# encore_Main_Board_v2.net
KiCad netlist of a schematic drawn in EAGLE
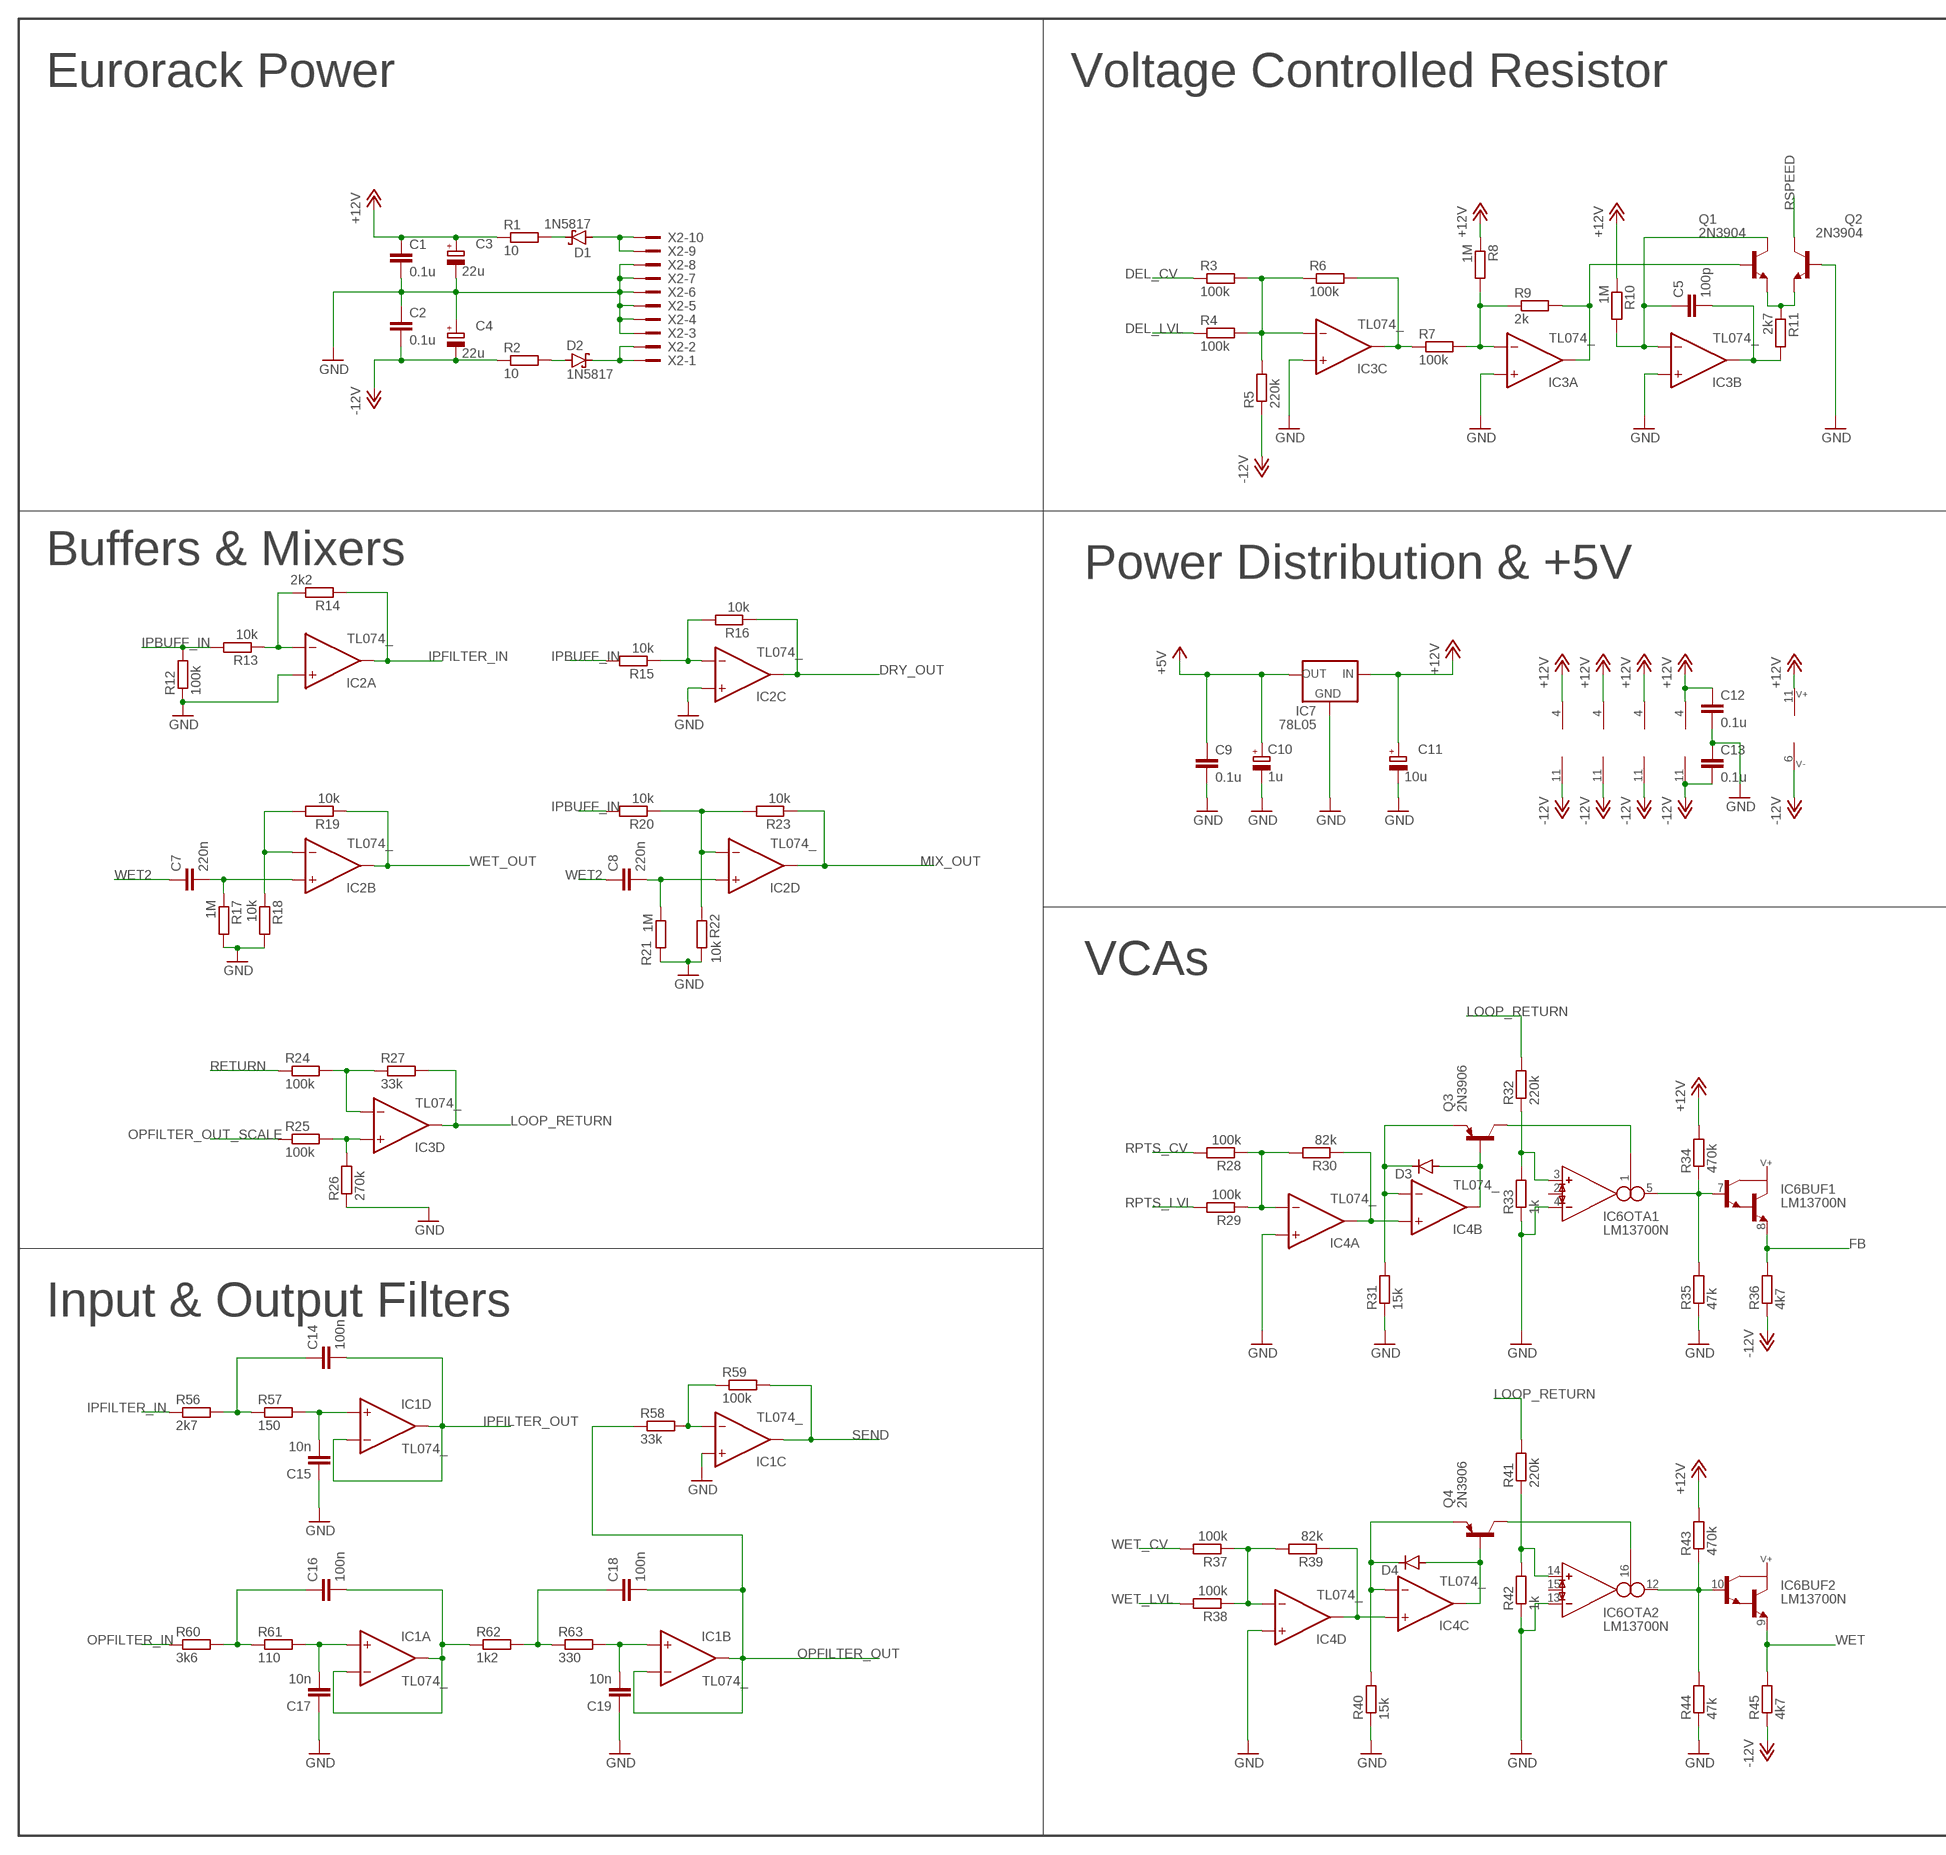
[diagram p0: schematic, sheet 1, part 1 of 2]
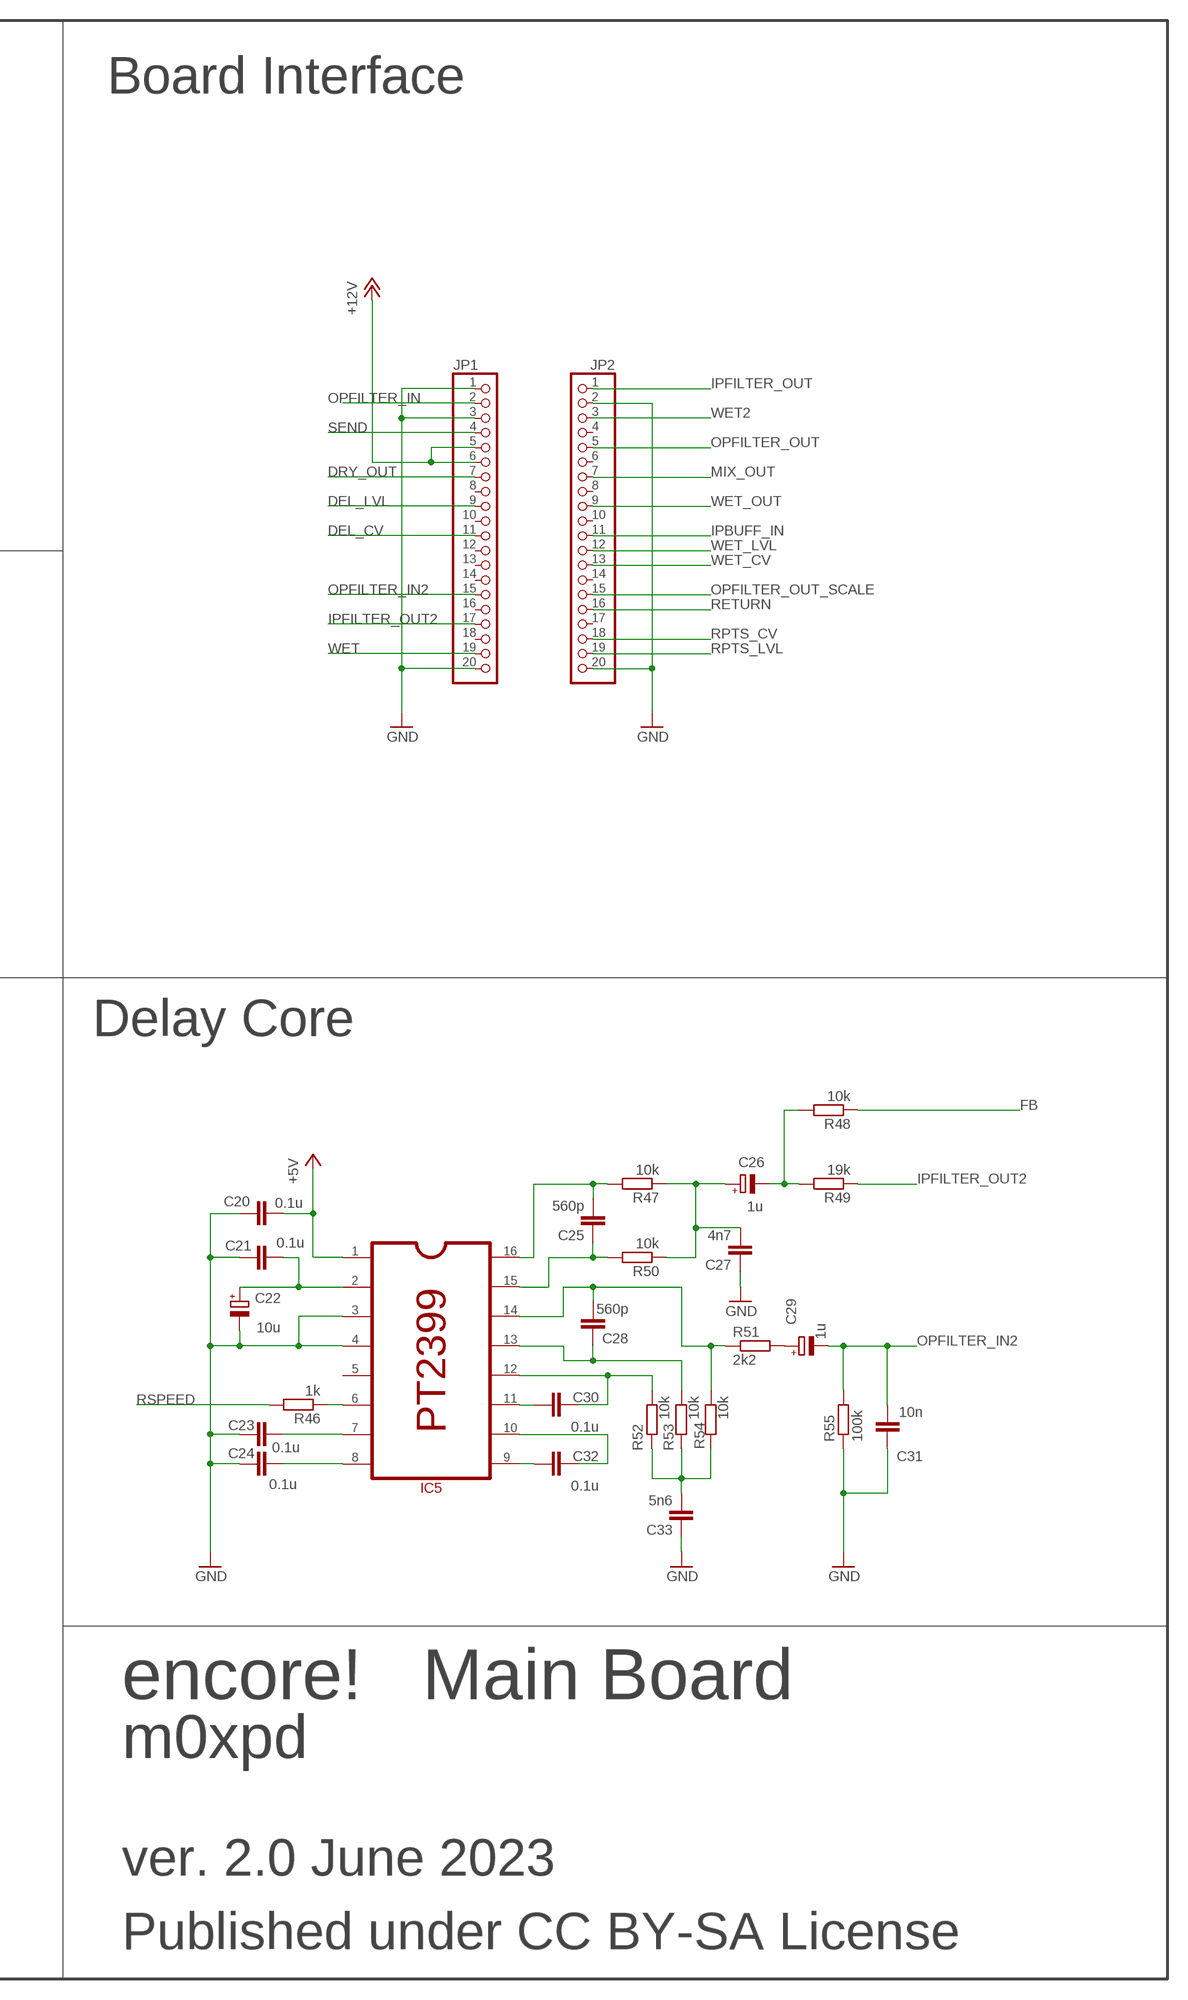
[diagram p1: schematic, sheet 1, part 2 of 2]

(export (version "E")
  (design (tool "Eeschema 10.0.6"))
  (components
    (comp (ref "C1")
      (value "0.1u")
      (footprint "eagle-import:C050-025X075")
      (libsource (lib "eagle-import") (part "C-EU050-025X075"))
    )
    (comp (ref "C2")
      (value "0.1u")
      (footprint "eagle-import:C050-025X075")
      (libsource (lib "eagle-import") (part "C-EU050-025X075"))
    )
    (comp (ref "C3")
      (value "22u")
      (footprint "eagle-import:E2,5-5")
      (libsource (lib "eagle-import") (part "CPOL-EUE2.5-5"))
    )
    (comp (ref "C4")
      (value "22u")
      (footprint "eagle-import:E2,5-5")
      (libsource (lib "eagle-import") (part "CPOL-EUE2.5-5"))
    )
    (comp (ref "C5")
      (value "100p")
      (footprint "eagle-import:C025-025X050")
      (libsource (lib "eagle-import") (part "C-EU025-025X050"))
    )
    (comp (ref "C7")
      (value "220n")
      (footprint "eagle-import:C050-024X044")
      (libsource (lib "eagle-import") (part "C-EU050-024X044"))
    )
    (comp (ref "C8")
      (value "220n")
      (footprint "eagle-import:C050-024X044")
      (libsource (lib "eagle-import") (part "C-EU050-024X044"))
    )
    (comp (ref "C9")
      (value "0.1u")
      (footprint "eagle-import:C050-025X075")
      (libsource (lib "eagle-import") (part "C-EU050-025X075"))
    )
    (comp (ref "C10")
      (value "1u")
      (footprint "eagle-import:E2,5-5")
      (libsource (lib "eagle-import") (part "CPOL-EUE2.5-5"))
    )
    (comp (ref "C11")
      (value "10u")
      (footprint "eagle-import:E2,5-5")
      (libsource (lib "eagle-import") (part "CPOL-EUE2.5-5"))
    )
    (comp (ref "C12")
      (value "0.1u")
      (footprint "eagle-import:C050-025X075")
      (libsource (lib "eagle-import") (part "C-EU050-025X075"))
    )
    (comp (ref "C13")
      (value "0.1u")
      (footprint "eagle-import:C050-025X075")
      (libsource (lib "eagle-import") (part "C-EU050-025X075"))
    )
    (comp (ref "C14")
      (value "100n")
      (footprint "eagle-import:C025-025X050")
      (libsource (lib "eagle-import") (part "C-EU025-025X050"))
    )
    (comp (ref "C15")
      (value "10n")
      (footprint "eagle-import:C025-025X050")
      (libsource (lib "eagle-import") (part "C-EU025-025X050"))
    )
    (comp (ref "C16")
      (value "100n")
      (footprint "eagle-import:C025-025X050")
      (libsource (lib "eagle-import") (part "C-EU025-025X050"))
    )
    (comp (ref "C17")
      (value "10n")
      (footprint "eagle-import:C025-025X050")
      (libsource (lib "eagle-import") (part "C-EU025-025X050"))
    )
    (comp (ref "C18")
      (value "100n")
      (footprint "eagle-import:C025-025X050")
      (libsource (lib "eagle-import") (part "C-EU025-025X050"))
    )
    (comp (ref "C19")
      (value "10n")
      (footprint "eagle-import:C025-025X050")
      (libsource (lib "eagle-import") (part "C-EU025-025X050"))
    )
    (comp (ref "C20")
      (value "0.1u")
      (footprint "eagle-import:C050-025X075")
      (libsource (lib "eagle-import") (part "C-EU050-025X075"))
    )
    (comp (ref "C21")
      (value "0.1u")
      (footprint "eagle-import:C050-025X075")
      (libsource (lib "eagle-import") (part "C-EU050-025X075"))
    )
    (comp (ref "C22")
      (value "10u")
      (footprint "eagle-import:E2,5-5")
      (libsource (lib "eagle-import") (part "CPOL-EUE2.5-5"))
    )
    (comp (ref "C23")
      (value "0.1u")
      (footprint "eagle-import:C050-025X075")
      (libsource (lib "eagle-import") (part "C-EU050-025X075"))
    )
    (comp (ref "C24")
      (value "0.1u")
      (footprint "eagle-import:C050-025X075")
      (libsource (lib "eagle-import") (part "C-EU050-025X075"))
    )
    (comp (ref "C25")
      (value "560p")
      (footprint "eagle-import:C025-025X050")
      (libsource (lib "eagle-import") (part "C-EU025-025X050"))
    )
    (comp (ref "C26")
      (value "1u")
      (footprint "eagle-import:E2,5-5")
      (libsource (lib "eagle-import") (part "CPOL-EUE2.5-5"))
    )
    (comp (ref "C27")
      (value "4n7")
      (footprint "eagle-import:C050-025X075")
      (libsource (lib "eagle-import") (part "C-EU050-025X075"))
    )
    (comp (ref "C28")
      (value "560p")
      (footprint "eagle-import:C025-025X050")
      (libsource (lib "eagle-import") (part "C-EU025-025X050"))
    )
    (comp (ref "C29")
      (value "1u")
      (footprint "eagle-import:E2,5-5")
      (libsource (lib "eagle-import") (part "CPOL-EUE2.5-5"))
    )
    (comp (ref "C30")
      (value "0.1u")
      (footprint "eagle-import:C050-025X075")
      (libsource (lib "eagle-import") (part "C-EU050-025X075"))
    )
    (comp (ref "C31")
      (value "10n")
      (footprint "eagle-import:C025-025X050")
      (libsource (lib "eagle-import") (part "C-EU025-025X050"))
    )
    (comp (ref "C32")
      (value "0.1u")
      (footprint "eagle-import:C050-025X075")
      (libsource (lib "eagle-import") (part "C-EU050-025X075"))
    )
    (comp (ref "C33")
      (value "5n6")
      (footprint "eagle-import:C050-025X075")
      (libsource (lib "eagle-import") (part "C-EU050-025X075"))
    )
    (comp (ref "D1")
      (value "1N5817")
      (footprint "eagle-import:DO35-7")
      (libsource (lib "eagle-import") (part "SCHOTTKY-DIODEDO35-7"))
    )
    (comp (ref "D2")
      (value "1N5817")
      (footprint "eagle-import:DO35-7")
      (libsource (lib "eagle-import") (part "SCHOTTKY-DIODEDO35-7"))
    )
    (comp (ref "D3")
      (value "1N4148DO35-7")
      (footprint "eagle-import:DO35-7")
      (libsource (lib "eagle-import") (part "1N4148DO35-7"))
    )
    (comp (ref "D4")
      (value "1N4148DO35-7")
      (footprint "eagle-import:DO35-7")
      (libsource (lib "eagle-import") (part "1N4148DO35-7"))
    )
    (comp (ref "IC1")
      (value "TL074_")
      (footprint "eagle-import:DIL14")
      (libsource (lib "eagle-import") (part "TL074_"))
    )
    (comp (ref "IC2")
      (value "TL074_")
      (footprint "eagle-import:DIL14")
      (libsource (lib "eagle-import") (part "TL074_"))
    )
    (comp (ref "IC3")
      (value "TL074_")
      (footprint "eagle-import:DIL14")
      (libsource (lib "eagle-import") (part "TL074_"))
    )
    (comp (ref "IC4")
      (value "TL074_")
      (footprint "eagle-import:DIL14")
      (libsource (lib "eagle-import") (part "TL074_"))
    )
    (comp (ref "IC5")
      (value "PT2399")
      (footprint "eagle-import:DIP-16")
      (libsource (lib "eagle-import") (part "PT2399"))
    )
    (comp (ref "IC6")
      (value "LM13700N")
      (footprint "eagle-import:DIL16")
      (libsource (lib "eagle-import") (part "LM13700N"))
    )
    (comp (ref "IC7")
      (value "78L05")
      (footprint "eagle-import:78LXX")
      (libsource (lib "eagle-import") (part "78LXX"))
    )
    (comp (ref "JP1")
      (value "PINHD-1X20")
      (footprint "eagle-import:1X20")
      (libsource (lib "eagle-import") (part "PINHD-1X20"))
    )
    (comp (ref "JP2")
      (value "PINHD-1X20")
      (footprint "eagle-import:1X20")
      (libsource (lib "eagle-import") (part "PINHD-1X20"))
    )
    (comp (ref "Q1")
      (value "2N3904")
      (footprint "eagle-import:TO92")
      (libsource (lib "eagle-import") (part "2N3904"))
    )
    (comp (ref "Q2")
      (value "2N3904")
      (footprint "eagle-import:TO92")
      (libsource (lib "eagle-import") (part "2N3904"))
    )
    (comp (ref "Q3")
      (value "2N3906")
      (footprint "eagle-import:TO92")
      (libsource (lib "eagle-import") (part "2N3906"))
    )
    (comp (ref "Q4")
      (value "2N3906")
      (footprint "eagle-import:TO92")
      (libsource (lib "eagle-import") (part "2N3906"))
    )
    (comp (ref "R1")
      (value "10")
      (footprint "eagle-import:0204_7")
      (libsource (lib "eagle-import") (part "R-EU_0204/7"))
    )
    (comp (ref "R2")
      (value "10")
      (footprint "eagle-import:0204_7")
      (libsource (lib "eagle-import") (part "R-EU_0204/7"))
    )
    (comp (ref "R3")
      (value "100k")
      (footprint "eagle-import:0204_7")
      (libsource (lib "eagle-import") (part "R-EU_0204/7"))
    )
    (comp (ref "R4")
      (value "100k")
      (footprint "eagle-import:0204_7")
      (libsource (lib "eagle-import") (part "R-EU_0204/7"))
    )
    (comp (ref "R5")
      (value "220k")
      (footprint "eagle-import:0204_7")
      (libsource (lib "eagle-import") (part "R-EU_0204/7"))
    )
    (comp (ref "R6")
      (value "100k")
      (footprint "eagle-import:0204_7")
      (libsource (lib "eagle-import") (part "R-EU_0204/7"))
    )
    (comp (ref "R7")
      (value "100k")
      (footprint "eagle-import:0204_7")
      (libsource (lib "eagle-import") (part "R-EU_0204/7"))
    )
    (comp (ref "R8")
      (value "1M")
      (footprint "eagle-import:0204_7")
      (libsource (lib "eagle-import") (part "R-EU_0204/7"))
    )
    (comp (ref "R9")
      (value "2k")
      (footprint "eagle-import:0204_7")
      (libsource (lib "eagle-import") (part "R-EU_0204/7"))
    )
    (comp (ref "R10")
      (value "1M")
      (footprint "eagle-import:0204_7")
      (libsource (lib "eagle-import") (part "R-EU_0204/7"))
    )
    (comp (ref "R11")
      (value "2k7")
      (footprint "eagle-import:0204_7")
      (libsource (lib "eagle-import") (part "R-EU_0204/7"))
    )
    (comp (ref "R12")
      (value "100k")
      (footprint "eagle-import:0204_7")
      (libsource (lib "eagle-import") (part "R-EU_0204/7"))
    )
    (comp (ref "R13")
      (value "10k")
      (footprint "eagle-import:0204_7")
      (libsource (lib "eagle-import") (part "R-EU_0204/7"))
    )
    (comp (ref "R14")
      (value "2k2")
      (footprint "eagle-import:0204_7")
      (libsource (lib "eagle-import") (part "R-EU_0204/7"))
    )
    (comp (ref "R15")
      (value "10k")
      (footprint "eagle-import:0204_7")
      (libsource (lib "eagle-import") (part "R-EU_0204/7"))
    )
    (comp (ref "R16")
      (value "10k")
      (footprint "eagle-import:0204_7")
      (libsource (lib "eagle-import") (part "R-EU_0204/7"))
    )
    (comp (ref "R17")
      (value "1M")
      (footprint "eagle-import:0204_7")
      (libsource (lib "eagle-import") (part "R-EU_0204/7"))
    )
    (comp (ref "R18")
      (value "10k")
      (footprint "eagle-import:0204_7")
      (libsource (lib "eagle-import") (part "R-EU_0204/7"))
    )
    (comp (ref "R19")
      (value "10k")
      (footprint "eagle-import:0204_7")
      (libsource (lib "eagle-import") (part "R-EU_0204/7"))
    )
    (comp (ref "R20")
      (value "10k")
      (footprint "eagle-import:0204_7")
      (libsource (lib "eagle-import") (part "R-EU_0204/7"))
    )
    (comp (ref "R21")
      (value "1M")
      (footprint "eagle-import:0204_7")
      (libsource (lib "eagle-import") (part "R-EU_0204/7"))
    )
    (comp (ref "R22")
      (value "10k")
      (footprint "eagle-import:0204_7")
      (libsource (lib "eagle-import") (part "R-EU_0204/7"))
    )
    (comp (ref "R23")
      (value "10k")
      (footprint "eagle-import:0204_7")
      (libsource (lib "eagle-import") (part "R-EU_0204/7"))
    )
    (comp (ref "R24")
      (value "100k")
      (footprint "eagle-import:0204_7")
      (libsource (lib "eagle-import") (part "R-EU_0204/7"))
    )
    (comp (ref "R25")
      (value "100k")
      (footprint "eagle-import:0204_7")
      (libsource (lib "eagle-import") (part "R-EU_0204/7"))
    )
    (comp (ref "R26")
      (value "270k")
      (footprint "eagle-import:0204_7")
      (libsource (lib "eagle-import") (part "R-EU_0204/7"))
    )
    (comp (ref "R27")
      (value "33k")
      (footprint "eagle-import:0204_7")
      (libsource (lib "eagle-import") (part "R-EU_0204/7"))
    )
    (comp (ref "R28")
      (value "100k")
      (footprint "eagle-import:0204_7")
      (libsource (lib "eagle-import") (part "R-EU_0204/7"))
    )
    (comp (ref "R29")
      (value "100k")
      (footprint "eagle-import:0204_7")
      (libsource (lib "eagle-import") (part "R-EU_0204/7"))
    )
    (comp (ref "R30")
      (value "82k")
      (footprint "eagle-import:0204_7")
      (libsource (lib "eagle-import") (part "R-EU_0204/7"))
    )
    (comp (ref "R31")
      (value "15k")
      (footprint "eagle-import:0204_7")
      (libsource (lib "eagle-import") (part "R-EU_0204/7"))
    )
    (comp (ref "R32")
      (value "220k")
      (footprint "eagle-import:0204_7")
      (libsource (lib "eagle-import") (part "R-EU_0204/7"))
    )
    (comp (ref "R33")
      (value "1k")
      (footprint "eagle-import:0204_7")
      (libsource (lib "eagle-import") (part "R-EU_0204/7"))
    )
    (comp (ref "R34")
      (value "470k")
      (footprint "eagle-import:0204_7")
      (libsource (lib "eagle-import") (part "R-EU_0204/7"))
    )
    (comp (ref "R35")
      (value "47k")
      (footprint "eagle-import:0204_7")
      (libsource (lib "eagle-import") (part "R-EU_0204/7"))
    )
    (comp (ref "R36")
      (value "4k7")
      (footprint "eagle-import:0204_7")
      (libsource (lib "eagle-import") (part "R-EU_0204/7"))
    )
    (comp (ref "R37")
      (value "100k")
      (footprint "eagle-import:0204_7")
      (libsource (lib "eagle-import") (part "R-EU_0204/7"))
    )
    (comp (ref "R38")
      (value "100k")
      (footprint "eagle-import:0204_7")
      (libsource (lib "eagle-import") (part "R-EU_0204/7"))
    )
    (comp (ref "R39")
      (value "82k")
      (footprint "eagle-import:0204_7")
      (libsource (lib "eagle-import") (part "R-EU_0204/7"))
    )
    (comp (ref "R40")
      (value "15k")
      (footprint "eagle-import:0204_7")
      (libsource (lib "eagle-import") (part "R-EU_0204/7"))
    )
    (comp (ref "R41")
      (value "220k")
      (footprint "eagle-import:0204_7")
      (libsource (lib "eagle-import") (part "R-EU_0204/7"))
    )
    (comp (ref "R42")
      (value "1k")
      (footprint "eagle-import:0204_7")
      (libsource (lib "eagle-import") (part "R-EU_0204/7"))
    )
    (comp (ref "R43")
      (value "470k")
      (footprint "eagle-import:0204_7")
      (libsource (lib "eagle-import") (part "R-EU_0204/7"))
    )
    (comp (ref "R44")
      (value "47k")
      (footprint "eagle-import:0204_7")
      (libsource (lib "eagle-import") (part "R-EU_0204/7"))
    )
    (comp (ref "R45")
      (value "4k7")
      (footprint "eagle-import:0204_7")
      (libsource (lib "eagle-import") (part "R-EU_0204/7"))
    )
    (comp (ref "R46")
      (value "1k")
      (footprint "eagle-import:0204_7")
      (libsource (lib "eagle-import") (part "R-EU_0204/7"))
    )
    (comp (ref "R47")
      (value "10k")
      (footprint "eagle-import:0204_7")
      (libsource (lib "eagle-import") (part "R-EU_0204/7"))
    )
    (comp (ref "R48")
      (value "10k")
      (footprint "eagle-import:0204_7")
      (libsource (lib "eagle-import") (part "R-EU_0204/7"))
    )
    (comp (ref "R49")
      (value "19k")
      (footprint "eagle-import:0204_7")
      (libsource (lib "eagle-import") (part "R-EU_0204/7"))
    )
    (comp (ref "R50")
      (value "10k")
      (footprint "eagle-import:0204_7")
      (libsource (lib "eagle-import") (part "R-EU_0204/7"))
    )
    (comp (ref "R51")
      (value "2k2")
      (footprint "eagle-import:0204_7")
      (libsource (lib "eagle-import") (part "R-EU_0204/7"))
    )
    (comp (ref "R52")
      (value "10k")
      (footprint "eagle-import:0204_7")
      (libsource (lib "eagle-import") (part "R-EU_0204/7"))
    )
    (comp (ref "R53")
      (value "10k")
      (footprint "eagle-import:0204_7")
      (libsource (lib "eagle-import") (part "R-EU_0204/7"))
    )
    (comp (ref "R54")
      (value "10k")
      (footprint "eagle-import:0204_7")
      (libsource (lib "eagle-import") (part "R-EU_0204/7"))
    )
    (comp (ref "R55")
      (value "100k")
      (footprint "eagle-import:0204_7")
      (libsource (lib "eagle-import") (part "R-EU_0204/7"))
    )
    (comp (ref "R56")
      (value "2k7")
      (footprint "eagle-import:0204_7")
      (libsource (lib "eagle-import") (part "R-EU_0204/7"))
    )
    (comp (ref "R57")
      (value "150")
      (footprint "eagle-import:0204_7")
      (libsource (lib "eagle-import") (part "R-EU_0204/7"))
    )
    (comp (ref "R58")
      (value "33k")
      (footprint "eagle-import:0204_7")
      (libsource (lib "eagle-import") (part "R-EU_0204/7"))
    )
    (comp (ref "R59")
      (value "100k")
      (footprint "eagle-import:0204_7")
      (libsource (lib "eagle-import") (part "R-EU_0204/7"))
    )
    (comp (ref "R60")
      (value "3k6")
      (footprint "eagle-import:0204_7")
      (libsource (lib "eagle-import") (part "R-EU_0204/7"))
    )
    (comp (ref "R61")
      (value "110")
      (footprint "eagle-import:0204_7")
      (libsource (lib "eagle-import") (part "R-EU_0204/7"))
    )
    (comp (ref "R62")
      (value "1k2")
      (footprint "eagle-import:0204_7")
      (libsource (lib "eagle-import") (part "R-EU_0204/7"))
    )
    (comp (ref "R63")
      (value "330")
      (footprint "eagle-import:0204_7")
      (libsource (lib "eagle-import") (part "R-EU_0204/7"))
    )
    (comp (ref "X2")
      (value "2510-")
      (footprint "eagle-import:PAK100_2500-10")
      (fields (field (name "MF") "3M") (field (name "MPN") "2510-6002UB"))
      (libsource (lib "eagle-import") (part "2510-"))
    )
  )
  (nets
    (net (code "1") (name "+5V") (class "Default")
      (node (ref "C10") (pin "+") (pinfunction "+_+") (pintype "passive"))
      (node (ref "C20") (pin "2") (pinfunction "2_2") (pintype "passive"))
      (node (ref "C9") (pin "1") (pinfunction "1_1") (pintype "passive"))
      (node (ref "IC5") (pin "1") (pinfunction "1_1") (pintype "bidirectional"))
      (node (ref "IC7") (pin "OUT") (pinfunction "OUT_OUT") (pintype "passive"))
    )
    (net (code "2") (name "+12V") (class "Default")
      (node (ref "C1") (pin "1") (pinfunction "1_1") (pintype "passive"))
      (node (ref "C11") (pin "+") (pinfunction "+_+") (pintype "passive"))
      (node (ref "C12") (pin "1") (pinfunction "1_1") (pintype "passive"))
      (node (ref "C3") (pin "+") (pinfunction "+_+") (pintype "passive"))
      (node (ref "IC1") (pin "4") (pinfunction "V+_4") (pintype "power_in"))
      (node (ref "IC2") (pin "4") (pinfunction "V+_4") (pintype "power_in"))
      (node (ref "IC3") (pin "4") (pinfunction "V+_4") (pintype "power_in"))
      (node (ref "IC4") (pin "4") (pinfunction "V+_4") (pintype "power_in"))
      (node (ref "IC6") (pin "11") (pinfunction "V+_11") (pintype "power_in"))
      (node (ref "IC7") (pin "IN") (pinfunction "IN_IN") (pintype "input"))
      (node (ref "JP1") (pin "5") (pinfunction "5_5") (pintype "passive"))
      (node (ref "JP1") (pin "6") (pinfunction "6_6") (pintype "passive"))
      (node (ref "R1") (pin "1") (pinfunction "1_1") (pintype "passive"))
      (node (ref "R10") (pin "1") (pinfunction "1_1") (pintype "passive"))
      (node (ref "R34") (pin "2") (pinfunction "2_2") (pintype "passive"))
      (node (ref "R43") (pin "2") (pinfunction "2_2") (pintype "passive"))
      (node (ref "R8") (pin "1") (pinfunction "1_1") (pintype "passive"))
    )
    (net (code "3") (name "-12V") (class "Default")
      (node (ref "C13") (pin "2") (pinfunction "2_2") (pintype "passive"))
      (node (ref "C2") (pin "2") (pinfunction "2_2") (pintype "passive"))
      (node (ref "C4") (pin "-") (pinfunction "-_-") (pintype "passive"))
      (node (ref "IC1") (pin "11") (pinfunction "V-_11") (pintype "power_in"))
      (node (ref "IC2") (pin "11") (pinfunction "V-_11") (pintype "power_in"))
      (node (ref "IC3") (pin "11") (pinfunction "V-_11") (pintype "power_in"))
      (node (ref "IC4") (pin "11") (pinfunction "V-_11") (pintype "power_in"))
      (node (ref "IC6") (pin "6") (pinfunction "V-_6") (pintype "power_in"))
      (node (ref "R2") (pin "1") (pinfunction "1_1") (pintype "passive"))
      (node (ref "R36") (pin "1") (pinfunction "1_1") (pintype "passive"))
      (node (ref "R45") (pin "1") (pinfunction "1_1") (pintype "passive"))
      (node (ref "R5") (pin "1") (pinfunction "1_1") (pintype "passive"))
    )
    (net (code "4") (name "/DEL_CV") (class "Default")
      (node (ref "JP1") (pin "11") (pinfunction "11_11") (pintype "passive"))
      (node (ref "R3") (pin "1") (pinfunction "1_1") (pintype "passive"))
    )
    (net (code "5") (name "/DEL_LVL") (class "Default")
      (node (ref "JP1") (pin "9") (pinfunction "9_9") (pintype "passive"))
      (node (ref "R4") (pin "1") (pinfunction "1_1") (pintype "passive"))
    )
    (net (code "6") (name "/DRY_OUT") (class "Default")
      (node (ref "IC2") (pin "8") (pinfunction "OUT_8") (pintype "output"))
      (node (ref "JP1") (pin "7") (pinfunction "7_7") (pintype "passive"))
      (node (ref "R16") (pin "1") (pinfunction "1_1") (pintype "passive"))
    )
    (net (code "7") (name "/FB") (class "Default")
      (node (ref "IC6") (pin "8") (pinfunction "E_8") (pintype "passive"))
      (node (ref "R36") (pin "2") (pinfunction "2_2") (pintype "passive"))
      (node (ref "R48") (pin "1") (pinfunction "1_1") (pintype "passive"))
    )
    (net (code "8") (name "/IPBUFF_IN") (class "Default")
      (node (ref "JP2") (pin "11") (pinfunction "11_11") (pintype "passive"))
      (node (ref "R12") (pin "2") (pinfunction "2_2") (pintype "passive"))
      (node (ref "R13") (pin "2") (pinfunction "2_2") (pintype "passive"))
      (node (ref "R15") (pin "2") (pinfunction "2_2") (pintype "passive"))
      (node (ref "R20") (pin "2") (pinfunction "2_2") (pintype "passive"))
    )
    (net (code "9") (name "/IPFILTER_IN") (class "Default")
      (node (ref "IC2") (pin "1") (pinfunction "OUT_1") (pintype "output"))
      (node (ref "R14") (pin "1") (pinfunction "1_1") (pintype "passive"))
      (node (ref "R56") (pin "1") (pinfunction "1_1") (pintype "passive"))
    )
    (net (code "10") (name "/IPFILTER_OUT") (class "Default")
      (node (ref "C14") (pin "2") (pinfunction "2_2") (pintype "passive"))
      (node (ref "IC1") (pin "13") (pinfunction "-IN_13") (pintype "input"))
      (node (ref "IC1") (pin "14") (pinfunction "OUT_14") (pintype "output"))
      (node (ref "JP2") (pin "1") (pinfunction "1_1") (pintype "passive"))
    )
    (net (code "11") (name "/IPFILTER_OUT2") (class "Default")
      (node (ref "JP1") (pin "17") (pinfunction "17_17") (pintype "passive"))
      (node (ref "R49") (pin "1") (pinfunction "1_1") (pintype "passive"))
    )
    (net (code "12") (name "/LOOP_RETURN") (class "Default")
      (node (ref "IC3") (pin "14") (pinfunction "OUT_14") (pintype "output"))
      (node (ref "R27") (pin "2") (pinfunction "2_2") (pintype "passive"))
      (node (ref "R32") (pin "2") (pinfunction "2_2") (pintype "passive"))
      (node (ref "R41") (pin "2") (pinfunction "2_2") (pintype "passive"))
    )
    (net (code "13") (name "/MIX_OUT") (class "Default")
      (node (ref "IC2") (pin "14") (pinfunction "OUT_14") (pintype "output"))
      (node (ref "JP2") (pin "7") (pinfunction "7_7") (pintype "passive"))
      (node (ref "R23") (pin "1") (pinfunction "1_1") (pintype "passive"))
    )
    (net (code "14") (name "/OPFILTER_IN") (class "Default")
      (node (ref "JP1") (pin "2") (pinfunction "2_2") (pintype "passive"))
      (node (ref "R60") (pin "1") (pinfunction "1_1") (pintype "passive"))
    )
    (net (code "15") (name "/OPFILTER_IN2") (class "Default")
      (node (ref "C29") (pin "-") (pinfunction "-_-") (pintype "passive"))
      (node (ref "C31") (pin "2") (pinfunction "2_2") (pintype "passive"))
      (node (ref "JP1") (pin "15") (pinfunction "15_15") (pintype "passive"))
      (node (ref "R55") (pin "2") (pinfunction "2_2") (pintype "passive"))
    )
    (net (code "16") (name "/OPFILTER_OUT") (class "Default")
      (node (ref "C18") (pin "2") (pinfunction "2_2") (pintype "passive"))
      (node (ref "IC1") (pin "6") (pinfunction "-IN_6") (pintype "input"))
      (node (ref "IC1") (pin "7") (pinfunction "OUT_7") (pintype "output"))
      (node (ref "JP2") (pin "5") (pinfunction "5_5") (pintype "passive"))
      (node (ref "R58") (pin "1") (pinfunction "1_1") (pintype "passive"))
    )
    (net (code "17") (name "/OPFILTER_OUT_SCALE") (class "Default")
      (node (ref "JP2") (pin "15") (pinfunction "15_15") (pintype "passive"))
      (node (ref "R25") (pin "1") (pinfunction "1_1") (pintype "passive"))
    )
    (net (code "18") (name "/RETURN") (class "Default")
      (node (ref "JP2") (pin "16") (pinfunction "16_16") (pintype "passive"))
      (node (ref "R24") (pin "1") (pinfunction "1_1") (pintype "passive"))
    )
    (net (code "19") (name "/RPTS_CV") (class "Default")
      (node (ref "JP2") (pin "18") (pinfunction "18_18") (pintype "passive"))
      (node (ref "R28") (pin "2") (pinfunction "2_2") (pintype "passive"))
    )
    (net (code "20") (name "/RPTS_LVL") (class "Default")
      (node (ref "JP2") (pin "19") (pinfunction "19_19") (pintype "passive"))
      (node (ref "R29") (pin "2") (pinfunction "2_2") (pintype "passive"))
    )
    (net (code "21") (name "/RSPEED") (class "Default")
      (node (ref "Q2") (pin "1") (pinfunction "C_1") (pintype "passive"))
      (node (ref "R46") (pin "2") (pinfunction "2_2") (pintype "passive"))
    )
    (net (code "22") (name "/SEND") (class "Default")
      (node (ref "IC1") (pin "8") (pinfunction "OUT_8") (pintype "output"))
      (node (ref "JP1") (pin "4") (pinfunction "4_4") (pintype "passive"))
      (node (ref "R59") (pin "2") (pinfunction "2_2") (pintype "passive"))
    )
    (net (code "23") (name "/WET") (class "Default")
      (node (ref "IC6") (pin "9") (pinfunction "E_9") (pintype "passive"))
      (node (ref "JP1") (pin "19") (pinfunction "19_19") (pintype "passive"))
      (node (ref "R45") (pin "2") (pinfunction "2_2") (pintype "passive"))
    )
    (net (code "24") (name "/WET2") (class "Default")
      (node (ref "C7") (pin "1") (pinfunction "1_1") (pintype "passive"))
      (node (ref "C8") (pin "1") (pinfunction "1_1") (pintype "passive"))
      (node (ref "JP2") (pin "3") (pinfunction "3_3") (pintype "passive"))
    )
    (net (code "25") (name "/WET_CV") (class "Default")
      (node (ref "JP2") (pin "13") (pinfunction "13_13") (pintype "passive"))
      (node (ref "R37") (pin "2") (pinfunction "2_2") (pintype "passive"))
    )
    (net (code "26") (name "/WET_LVL") (class "Default")
      (node (ref "JP2") (pin "12") (pinfunction "12_12") (pintype "passive"))
      (node (ref "R38") (pin "2") (pinfunction "2_2") (pintype "passive"))
    )
    (net (code "27") (name "/WET_OUT") (class "Default")
      (node (ref "IC2") (pin "7") (pinfunction "OUT_7") (pintype "output"))
      (node (ref "JP2") (pin "9") (pinfunction "9_9") (pintype "passive"))
      (node (ref "R19") (pin "1") (pinfunction "1_1") (pintype "passive"))
    )
    (net (code "28") (name "GND") (class "Default")
      (node (ref "C1") (pin "2") (pinfunction "2_2") (pintype "passive"))
      (node (ref "C10") (pin "-") (pinfunction "-_-") (pintype "passive"))
      (node (ref "C11") (pin "-") (pinfunction "-_-") (pintype "passive"))
      (node (ref "C12") (pin "2") (pinfunction "2_2") (pintype "passive"))
      (node (ref "C13") (pin "1") (pinfunction "1_1") (pintype "passive"))
      (node (ref "C15") (pin "1") (pinfunction "1_1") (pintype "passive"))
      (node (ref "C17") (pin "1") (pinfunction "1_1") (pintype "passive"))
      (node (ref "C19") (pin "1") (pinfunction "1_1") (pintype "passive"))
      (node (ref "C2") (pin "1") (pinfunction "1_1") (pintype "passive"))
      (node (ref "C20") (pin "1") (pinfunction "1_1") (pintype "passive"))
      (node (ref "C21") (pin "1") (pinfunction "1_1") (pintype "passive"))
      (node (ref "C22") (pin "-") (pinfunction "-_-") (pintype "passive"))
      (node (ref "C23") (pin "1") (pinfunction "1_1") (pintype "passive"))
      (node (ref "C24") (pin "1") (pinfunction "1_1") (pintype "passive"))
      (node (ref "C27") (pin "1") (pinfunction "1_1") (pintype "passive"))
      (node (ref "C3") (pin "-") (pinfunction "-_-") (pintype "passive"))
      (node (ref "C31") (pin "1") (pinfunction "1_1") (pintype "passive"))
      (node (ref "C33") (pin "1") (pinfunction "1_1") (pintype "passive"))
      (node (ref "C4") (pin "+") (pinfunction "+_+") (pintype "passive"))
      (node (ref "C9") (pin "2") (pinfunction "2_2") (pintype "passive"))
      (node (ref "IC1") (pin "10") (pinfunction "+IN_10") (pintype "input"))
      (node (ref "IC2") (pin "10") (pinfunction "+IN_10") (pintype "input"))
      (node (ref "IC2") (pin "3") (pinfunction "+IN_3") (pintype "input"))
      (node (ref "IC3") (pin "10") (pinfunction "+IN_10") (pintype "input"))
      (node (ref "IC3") (pin "3") (pinfunction "+IN_3") (pintype "input"))
      (node (ref "IC3") (pin "5") (pinfunction "+IN_5") (pintype "input"))
      (node (ref "IC4") (pin "12") (pinfunction "+IN_12") (pintype "input"))
      (node (ref "IC4") (pin "3") (pinfunction "+IN_3") (pintype "input"))
      (node (ref "IC5") (pin "3") (pinfunction "3_3") (pintype "bidirectional"))
      (node (ref "IC5") (pin "4") (pinfunction "4_4") (pintype "bidirectional"))
      (node (ref "IC6") (pin "13") (pinfunction "IN_N_13") (pintype "input"))
      (node (ref "IC6") (pin "4") (pinfunction "IN_N_4") (pintype "input"))
      (node (ref "IC7") (pin "GND") (pinfunction "GND_GND") (pintype "input"))
      (node (ref "JP1") (pin "1") (pinfunction "1_1") (pintype "passive"))
      (node (ref "JP1") (pin "20") (pinfunction "20_20") (pintype "passive"))
      (node (ref "JP1") (pin "3") (pinfunction "3_3") (pintype "passive"))
      (node (ref "JP2") (pin "2") (pinfunction "2_2") (pintype "passive"))
      (node (ref "JP2") (pin "20") (pinfunction "20_20") (pintype "passive"))
      (node (ref "Q2") (pin "2") (pinfunction "B_2") (pintype "passive"))
      (node (ref "R12") (pin "1") (pinfunction "1_1") (pintype "passive"))
      (node (ref "R17") (pin "2") (pinfunction "2_2") (pintype "passive"))
      (node (ref "R18") (pin "2") (pinfunction "2_2") (pintype "passive"))
      (node (ref "R21") (pin "2") (pinfunction "2_2") (pintype "passive"))
      (node (ref "R22") (pin "2") (pinfunction "2_2") (pintype "passive"))
      (node (ref "R26") (pin "1") (pinfunction "1_1") (pintype "passive"))
      (node (ref "R31") (pin "1") (pinfunction "1_1") (pintype "passive"))
      (node (ref "R33") (pin "1") (pinfunction "1_1") (pintype "passive"))
      (node (ref "R35") (pin "1") (pinfunction "1_1") (pintype "passive"))
      (node (ref "R40") (pin "1") (pinfunction "1_1") (pintype "passive"))
      (node (ref "R42") (pin "1") (pinfunction "1_1") (pintype "passive"))
      (node (ref "R44") (pin "1") (pinfunction "1_1") (pintype "passive"))
      (node (ref "R55") (pin "1") (pinfunction "1_1") (pintype "passive"))
      (node (ref "X2") (pin "3") (pinfunction "KL_3") (pintype "passive"))
      (node (ref "X2") (pin "4") (pinfunction "KL_4") (pintype "passive"))
      (node (ref "X2") (pin "5") (pinfunction "KL_5") (pintype "passive"))
      (node (ref "X2") (pin "6") (pinfunction "KL_6") (pintype "passive"))
      (node (ref "X2") (pin "7") (pinfunction "KL_7") (pintype "passive"))
      (node (ref "X2") (pin "8") (pinfunction "KL_8") (pintype "passive"))
    )
    (net (code "29") (name "Net-(C14-Pad1)") (class "Default")
      (node (ref "C14") (pin "1") (pinfunction "1_1") (pintype "passive"))
      (node (ref "R56") (pin "2") (pinfunction "2_2") (pintype "passive"))
      (node (ref "R57") (pin "1") (pinfunction "1_1") (pintype "passive"))
    )
    (net (code "30") (name "Net-(C16-Pad1)") (class "Default")
      (node (ref "C16") (pin "1") (pinfunction "1_1") (pintype "passive"))
      (node (ref "R60") (pin "2") (pinfunction "2_2") (pintype "passive"))
      (node (ref "R61") (pin "1") (pinfunction "1_1") (pintype "passive"))
    )
    (net (code "31") (name "Net-(C18-Pad1)") (class "Default")
      (node (ref "C18") (pin "1") (pinfunction "1_1") (pintype "passive"))
      (node (ref "R62") (pin "2") (pinfunction "2_2") (pintype "passive"))
      (node (ref "R63") (pin "1") (pinfunction "1_1") (pintype "passive"))
    )
    (net (code "32") (name "Net-(C21-Pad2)") (class "Default")
      (node (ref "C21") (pin "2") (pinfunction "2_2") (pintype "passive"))
      (node (ref "C22") (pin "+") (pinfunction "+_+") (pintype "passive"))
      (node (ref "IC5") (pin "2") (pinfunction "2_2") (pintype "bidirectional"))
    )
    (net (code "33") (name "Net-(C23-Pad2)") (class "Default")
      (node (ref "C23") (pin "2") (pinfunction "2_2") (pintype "passive"))
      (node (ref "IC5") (pin "7") (pinfunction "7_7") (pintype "bidirectional"))
    )
    (net (code "34") (name "Net-(C24-Pad2)") (class "Default")
      (node (ref "C24") (pin "2") (pinfunction "2_2") (pintype "passive"))
      (node (ref "IC5") (pin "8") (pinfunction "8_8") (pintype "bidirectional"))
    )
    (net (code "35") (name "Net-(C25-Pad1)") (class "Default")
      (node (ref "C25") (pin "1") (pinfunction "1_1") (pintype "passive"))
      (node (ref "IC5") (pin "15") (pinfunction "15_15") (pintype "bidirectional"))
      (node (ref "R50") (pin "2") (pinfunction "2_2") (pintype "passive"))
    )
    (net (code "36") (name "Net-(C25-Pad2)") (class "Default")
      (node (ref "C25") (pin "2") (pinfunction "2_2") (pintype "passive"))
      (node (ref "IC5") (pin "16") (pinfunction "16_16") (pintype "bidirectional"))
      (node (ref "R47") (pin "2") (pinfunction "2_2") (pintype "passive"))
    )
    (net (code "37") (name "Net-(C26-Pad+)") (class "Default")
      (node (ref "C26") (pin "+") (pinfunction "+_+") (pintype "passive"))
      (node (ref "C27") (pin "2") (pinfunction "2_2") (pintype "passive"))
      (node (ref "R47") (pin "1") (pinfunction "1_1") (pintype "passive"))
      (node (ref "R50") (pin "1") (pinfunction "1_1") (pintype "passive"))
    )
    (net (code "38") (name "Net-(C26-Pad-)") (class "Default")
      (node (ref "C26") (pin "-") (pinfunction "-_-") (pintype "passive"))
      (node (ref "R48") (pin "2") (pinfunction "2_2") (pintype "passive"))
      (node (ref "R49") (pin "2") (pinfunction "2_2") (pintype "passive"))
    )
    (net (code "39") (name "Net-(C28-Pad1)") (class "Default")
      (node (ref "C28") (pin "1") (pinfunction "1_1") (pintype "passive"))
      (node (ref "IC5") (pin "13") (pinfunction "13_13") (pintype "bidirectional"))
      (node (ref "R53") (pin "1") (pinfunction "1_1") (pintype "passive"))
    )
    (net (code "40") (name "Net-(C28-Pad2)") (class "Default")
      (node (ref "C28") (pin "2") (pinfunction "2_2") (pintype "passive"))
      (node (ref "IC5") (pin "14") (pinfunction "14_14") (pintype "bidirectional"))
      (node (ref "R51") (pin "1") (pinfunction "1_1") (pintype "passive"))
      (node (ref "R54") (pin "1") (pinfunction "1_1") (pintype "passive"))
    )
    (net (code "41") (name "Net-(C29-Pad+)") (class "Default")
      (node (ref "C29") (pin "+") (pinfunction "+_+") (pintype "passive"))
      (node (ref "R51") (pin "2") (pinfunction "2_2") (pintype "passive"))
    )
    (net (code "42") (name "Net-(C30-Pad1)") (class "Default")
      (node (ref "C30") (pin "1") (pinfunction "1_1") (pintype "passive"))
      (node (ref "IC5") (pin "11") (pinfunction "11_11") (pintype "bidirectional"))
    )
    (net (code "43") (name "Net-(C30-Pad2)") (class "Default")
      (node (ref "C30") (pin "2") (pinfunction "2_2") (pintype "passive"))
      (node (ref "IC5") (pin "12") (pinfunction "12_12") (pintype "bidirectional"))
      (node (ref "R52") (pin "1") (pinfunction "1_1") (pintype "passive"))
    )
    (net (code "44") (name "Net-(C32-Pad1)") (class "Default")
      (node (ref "C32") (pin "1") (pinfunction "1_1") (pintype "passive"))
      (node (ref "IC5") (pin "9") (pinfunction "9_9") (pintype "bidirectional"))
    )
    (net (code "45") (name "Net-(C32-Pad2)") (class "Default")
      (node (ref "C32") (pin "2") (pinfunction "2_2") (pintype "passive"))
      (node (ref "IC5") (pin "10") (pinfunction "10_10") (pintype "bidirectional"))
    )
    (net (code "46") (name "Net-(C33-Pad2)") (class "Default")
      (node (ref "C33") (pin "2") (pinfunction "2_2") (pintype "passive"))
      (node (ref "R52") (pin "2") (pinfunction "2_2") (pintype "passive"))
      (node (ref "R53") (pin "2") (pinfunction "2_2") (pintype "passive"))
      (node (ref "R54") (pin "2") (pinfunction "2_2") (pintype "passive"))
    )
    (net (code "47") (name "Net-(D1-PadC)") (class "Default")
      (node (ref "D1") (pin "C") (pinfunction "C_C") (pintype "passive"))
      (node (ref "R1") (pin "2") (pinfunction "2_2") (pintype "passive"))
    )
    (net (code "48") (name "Net-(D2-PadA)") (class "Default")
      (node (ref "D2") (pin "A") (pinfunction "A_A") (pintype "passive"))
      (node (ref "R2") (pin "2") (pinfunction "2_2") (pintype "passive"))
    )
    (net (code "49") (name "Net-(IC1A-+IN)") (class "Default")
      (node (ref "C17") (pin "2") (pinfunction "2_2") (pintype "passive"))
      (node (ref "IC1") (pin "3") (pinfunction "+IN_3") (pintype "input"))
      (node (ref "R61") (pin "2") (pinfunction "2_2") (pintype "passive"))
    )
    (net (code "50") (name "Net-(IC1A--IN)") (class "Default")
      (node (ref "C16") (pin "2") (pinfunction "2_2") (pintype "passive"))
      (node (ref "IC1") (pin "1") (pinfunction "OUT_1") (pintype "output"))
      (node (ref "IC1") (pin "2") (pinfunction "-IN_2") (pintype "input"))
      (node (ref "R62") (pin "1") (pinfunction "1_1") (pintype "passive"))
    )
    (net (code "51") (name "Net-(IC1B-+IN)") (class "Default")
      (node (ref "C19") (pin "2") (pinfunction "2_2") (pintype "passive"))
      (node (ref "IC1") (pin "5") (pinfunction "+IN_5") (pintype "input"))
      (node (ref "R63") (pin "2") (pinfunction "2_2") (pintype "passive"))
    )
    (net (code "52") (name "Net-(IC1C--IN)") (class "Default")
      (node (ref "IC1") (pin "9") (pinfunction "-IN_9") (pintype "input"))
      (node (ref "R58") (pin "2") (pinfunction "2_2") (pintype "passive"))
      (node (ref "R59") (pin "1") (pinfunction "1_1") (pintype "passive"))
    )
    (net (code "53") (name "Net-(IC1D-+IN)") (class "Default")
      (node (ref "C15") (pin "2") (pinfunction "2_2") (pintype "passive"))
      (node (ref "IC1") (pin "12") (pinfunction "+IN_12") (pintype "input"))
      (node (ref "R57") (pin "2") (pinfunction "2_2") (pintype "passive"))
    )
    (net (code "54") (name "Net-(IC2A--IN)") (class "Default")
      (node (ref "IC2") (pin "2") (pinfunction "-IN_2") (pintype "input"))
      (node (ref "R13") (pin "1") (pinfunction "1_1") (pintype "passive"))
      (node (ref "R14") (pin "2") (pinfunction "2_2") (pintype "passive"))
    )
    (net (code "55") (name "Net-(IC2B-+IN)") (class "Default")
      (node (ref "C7") (pin "2") (pinfunction "2_2") (pintype "passive"))
      (node (ref "IC2") (pin "5") (pinfunction "+IN_5") (pintype "input"))
      (node (ref "R17") (pin "1") (pinfunction "1_1") (pintype "passive"))
    )
    (net (code "56") (name "Net-(IC2B--IN)") (class "Default")
      (node (ref "IC2") (pin "6") (pinfunction "-IN_6") (pintype "input"))
      (node (ref "R18") (pin "1") (pinfunction "1_1") (pintype "passive"))
      (node (ref "R19") (pin "2") (pinfunction "2_2") (pintype "passive"))
    )
    (net (code "57") (name "Net-(IC2C--IN)") (class "Default")
      (node (ref "IC2") (pin "9") (pinfunction "-IN_9") (pintype "input"))
      (node (ref "R15") (pin "1") (pinfunction "1_1") (pintype "passive"))
      (node (ref "R16") (pin "2") (pinfunction "2_2") (pintype "passive"))
    )
    (net (code "58") (name "Net-(IC2D-+IN)") (class "Default")
      (node (ref "C8") (pin "2") (pinfunction "2_2") (pintype "passive"))
      (node (ref "IC2") (pin "12") (pinfunction "+IN_12") (pintype "input"))
      (node (ref "R21") (pin "1") (pinfunction "1_1") (pintype "passive"))
    )
    (net (code "59") (name "Net-(IC2D--IN)") (class "Default")
      (node (ref "IC2") (pin "13") (pinfunction "-IN_13") (pintype "input"))
      (node (ref "R20") (pin "1") (pinfunction "1_1") (pintype "passive"))
      (node (ref "R22") (pin "1") (pinfunction "1_1") (pintype "passive"))
      (node (ref "R23") (pin "2") (pinfunction "2_2") (pintype "passive"))
    )
    (net (code "60") (name "Net-(IC3A--IN)") (class "Default")
      (node (ref "IC3") (pin "2") (pinfunction "-IN_2") (pintype "input"))
      (node (ref "R7") (pin "2") (pinfunction "2_2") (pintype "passive"))
      (node (ref "R8") (pin "2") (pinfunction "2_2") (pintype "passive"))
      (node (ref "R9") (pin "1") (pinfunction "1_1") (pintype "passive"))
    )
    (net (code "61") (name "Net-(IC3A-OUT)") (class "Default")
      (node (ref "IC3") (pin "1") (pinfunction "OUT_1") (pintype "output"))
      (node (ref "Q1") (pin "2") (pinfunction "B_2") (pintype "passive"))
      (node (ref "R9") (pin "2") (pinfunction "2_2") (pintype "passive"))
    )
    (net (code "62") (name "Net-(IC3B--IN)") (class "Default")
      (node (ref "C5") (pin "1") (pinfunction "1_1") (pintype "passive"))
      (node (ref "IC3") (pin "6") (pinfunction "-IN_6") (pintype "input"))
      (node (ref "Q1") (pin "1") (pinfunction "C_1") (pintype "passive"))
      (node (ref "R10") (pin "2") (pinfunction "2_2") (pintype "passive"))
    )
    (net (code "63") (name "Net-(IC3B-OUT)") (class "Default")
      (node (ref "C5") (pin "2") (pinfunction "2_2") (pintype "passive"))
      (node (ref "IC3") (pin "7") (pinfunction "OUT_7") (pintype "output"))
      (node (ref "R11") (pin "2") (pinfunction "2_2") (pintype "passive"))
    )
    (net (code "64") (name "Net-(IC3C--IN)") (class "Default")
      (node (ref "IC3") (pin "9") (pinfunction "-IN_9") (pintype "input"))
      (node (ref "R3") (pin "2") (pinfunction "2_2") (pintype "passive"))
      (node (ref "R4") (pin "2") (pinfunction "2_2") (pintype "passive"))
      (node (ref "R5") (pin "2") (pinfunction "2_2") (pintype "passive"))
      (node (ref "R6") (pin "1") (pinfunction "1_1") (pintype "passive"))
    )
    (net (code "65") (name "Net-(IC3C-OUT)") (class "Default")
      (node (ref "IC3") (pin "8") (pinfunction "OUT_8") (pintype "output"))
      (node (ref "R6") (pin "2") (pinfunction "2_2") (pintype "passive"))
      (node (ref "R7") (pin "1") (pinfunction "1_1") (pintype "passive"))
    )
    (net (code "66") (name "Net-(IC3D-+IN)") (class "Default")
      (node (ref "IC3") (pin "12") (pinfunction "+IN_12") (pintype "input"))
      (node (ref "R25") (pin "2") (pinfunction "2_2") (pintype "passive"))
      (node (ref "R26") (pin "2") (pinfunction "2_2") (pintype "passive"))
    )
    (net (code "67") (name "Net-(IC3D--IN)") (class "Default")
      (node (ref "IC3") (pin "13") (pinfunction "-IN_13") (pintype "input"))
      (node (ref "R24") (pin "2") (pinfunction "2_2") (pintype "passive"))
      (node (ref "R27") (pin "1") (pinfunction "1_1") (pintype "passive"))
    )
    (net (code "68") (name "Net-(IC4A--IN)") (class "Default")
      (node (ref "IC4") (pin "2") (pinfunction "-IN_2") (pintype "input"))
      (node (ref "R28") (pin "1") (pinfunction "1_1") (pintype "passive"))
      (node (ref "R29") (pin "1") (pinfunction "1_1") (pintype "passive"))
      (node (ref "R30") (pin "2") (pinfunction "2_2") (pintype "passive"))
    )
    (net (code "69") (name "Net-(IC4A-OUT)") (class "Default")
      (node (ref "IC4") (pin "1") (pinfunction "OUT_1") (pintype "output"))
      (node (ref "IC4") (pin "5") (pinfunction "+IN_5") (pintype "input"))
      (node (ref "R30") (pin "1") (pinfunction "1_1") (pintype "passive"))
    )
    (net (code "70") (name "Net-(IC4B--IN)") (class "Default")
      (node (ref "D3") (pin "C") (pinfunction "C_C") (pintype "passive"))
      (node (ref "IC4") (pin "6") (pinfunction "-IN_6") (pintype "input"))
      (node (ref "Q3") (pin "3") (pinfunction "E_3") (pintype "passive"))
      (node (ref "R31") (pin "2") (pinfunction "2_2") (pintype "passive"))
    )
    (net (code "71") (name "Net-(IC4B-OUT)") (class "Default")
      (node (ref "D3") (pin "A") (pinfunction "A_A") (pintype "passive"))
      (node (ref "IC4") (pin "7") (pinfunction "OUT_7") (pintype "output"))
      (node (ref "Q3") (pin "2") (pinfunction "B_2") (pintype "passive"))
    )
    (net (code "72") (name "Net-(IC4C-+IN)") (class "Default")
      (node (ref "IC4") (pin "10") (pinfunction "+IN_10") (pintype "input"))
      (node (ref "IC4") (pin "14") (pinfunction "OUT_14") (pintype "output"))
      (node (ref "R39") (pin "1") (pinfunction "1_1") (pintype "passive"))
    )
    (net (code "73") (name "Net-(IC4C--IN)") (class "Default")
      (node (ref "D4") (pin "C") (pinfunction "C_C") (pintype "passive"))
      (node (ref "IC4") (pin "9") (pinfunction "-IN_9") (pintype "input"))
      (node (ref "Q4") (pin "3") (pinfunction "E_3") (pintype "passive"))
      (node (ref "R40") (pin "2") (pinfunction "2_2") (pintype "passive"))
    )
    (net (code "74") (name "Net-(IC4C-OUT)") (class "Default")
      (node (ref "D4") (pin "A") (pinfunction "A_A") (pintype "passive"))
      (node (ref "IC4") (pin "8") (pinfunction "OUT_8") (pintype "output"))
      (node (ref "Q4") (pin "2") (pinfunction "B_2") (pintype "passive"))
    )
    (net (code "75") (name "Net-(IC4D--IN)") (class "Default")
      (node (ref "IC4") (pin "13") (pinfunction "-IN_13") (pintype "input"))
      (node (ref "R37") (pin "1") (pinfunction "1_1") (pintype "passive"))
      (node (ref "R38") (pin "1") (pinfunction "1_1") (pintype "passive"))
      (node (ref "R39") (pin "2") (pinfunction "2_2") (pintype "passive"))
    )
    (net (code "76") (name "Net-(IC5-Pad6)") (class "Default")
      (node (ref "IC5") (pin "6") (pinfunction "6_6") (pintype "bidirectional"))
      (node (ref "R46") (pin "1") (pinfunction "1_1") (pintype "passive"))
    )
    (net (code "77") (name "Net-(IC6A-B)") (class "Default")
      (node (ref "IC6") (pin "5") (pinfunction "OUT_5") (pintype "output"))
      (node (ref "IC6") (pin "7") (pinfunction "B_7") (pintype "passive"))
      (node (ref "R34") (pin "1") (pinfunction "1_1") (pintype "passive"))
      (node (ref "R35") (pin "2") (pinfunction "2_2") (pintype "passive"))
    )
    (net (code "78") (name "Net-(IC6B-B)") (class "Default")
      (node (ref "IC6") (pin "10") (pinfunction "B_10") (pintype "passive"))
      (node (ref "IC6") (pin "12") (pinfunction "OUT_12") (pintype "output"))
      (node (ref "R43") (pin "1") (pinfunction "1_1") (pintype "passive"))
      (node (ref "R44") (pin "2") (pinfunction "2_2") (pintype "passive"))
    )
    (net (code "79") (name "Net-(IC6C-IN_P)") (class "Default")
      (node (ref "IC6") (pin "3") (pinfunction "IN_P_3") (pintype "input"))
      (node (ref "R32") (pin "1") (pinfunction "1_1") (pintype "passive"))
      (node (ref "R33") (pin "2") (pinfunction "2_2") (pintype "passive"))
    )
    (net (code "80") (name "Net-(IC6C-I_BIAS)") (class "Default")
      (node (ref "IC6") (pin "1") (pinfunction "I_BIAS_1") (pintype "input"))
      (node (ref "Q3") (pin "1") (pinfunction "C_1") (pintype "passive"))
    )
    (net (code "81") (name "Net-(IC6D-IN_P)") (class "Default")
      (node (ref "IC6") (pin "14") (pinfunction "IN_P_14") (pintype "input"))
      (node (ref "R41") (pin "1") (pinfunction "1_1") (pintype "passive"))
      (node (ref "R42") (pin "2") (pinfunction "2_2") (pintype "passive"))
    )
    (net (code "82") (name "Net-(IC6D-I_BIAS)") (class "Default")
      (node (ref "IC6") (pin "16") (pinfunction "I_BIAS_16") (pintype "input"))
      (node (ref "Q4") (pin "1") (pinfunction "C_1") (pintype "passive"))
    )
    (net (code "83") (name "Net-(Q1-E)") (class "Default")
      (node (ref "Q1") (pin "3") (pinfunction "E_3") (pintype "passive"))
      (node (ref "Q2") (pin "3") (pinfunction "E_3") (pintype "passive"))
      (node (ref "R11") (pin "1") (pinfunction "1_1") (pintype "passive"))
    )
    (net (code "84") (name "Net-(X2A-KL)") (class "Default")
      (node (ref "D2") (pin "C") (pinfunction "C_C") (pintype "passive"))
      (node (ref "X2") (pin "1") (pinfunction "KL_1") (pintype "passive"))
      (node (ref "X2") (pin "2") (pinfunction "KL_2") (pintype "passive"))
    )
    (net (code "85") (name "Net-(X2B-KL)") (class "Default")
      (node (ref "D1") (pin "A") (pinfunction "A_A") (pintype "passive"))
      (node (ref "X2") (pin "10") (pinfunction "KL_10") (pintype "passive"))
      (node (ref "X2") (pin "9") (pinfunction "KL_9") (pintype "passive"))
    )
    (net (code "86") (name "unconnected-(IC5-Pad5)") (class "Default")
      (node (ref "IC5") (pin "5") (pinfunction "5_5") (pintype "bidirectional"))
    )
    (net (code "87") (name "unconnected-(IC6C-I_DIODE-Pad2)") (class "Default")
      (node (ref "IC6") (pin "2") (pinfunction "I_DIODE_2") (pintype "input"))
    )
    (net (code "88") (name "unconnected-(IC6D-I_DIODE-Pad15)") (class "Default")
      (node (ref "IC6") (pin "15") (pinfunction "I_DIODE_15") (pintype "input"))
    )
    (net (code "89") (name "unconnected-(JP1-Pad8)") (class "Default")
      (node (ref "JP1") (pin "8") (pinfunction "8_8") (pintype "passive"))
    )
    (net (code "90") (name "unconnected-(JP1-Pad10)") (class "Default")
      (node (ref "JP1") (pin "10") (pinfunction "10_10") (pintype "passive"))
    )
    (net (code "91") (name "unconnected-(JP1-Pad12)") (class "Default")
      (node (ref "JP1") (pin "12") (pinfunction "12_12") (pintype "passive"))
    )
    (net (code "92") (name "unconnected-(JP1-Pad13)") (class "Default")
      (node (ref "JP1") (pin "13") (pinfunction "13_13") (pintype "passive"))
    )
    (net (code "93") (name "unconnected-(JP1-Pad14)") (class "Default")
      (node (ref "JP1") (pin "14") (pinfunction "14_14") (pintype "passive"))
    )
    (net (code "94") (name "unconnected-(JP1-Pad16)") (class "Default")
      (node (ref "JP1") (pin "16") (pinfunction "16_16") (pintype "passive"))
    )
    (net (code "95") (name "unconnected-(JP1-Pad18)") (class "Default")
      (node (ref "JP1") (pin "18") (pinfunction "18_18") (pintype "passive"))
    )
    (net (code "96") (name "unconnected-(JP2-Pad4)") (class "Default")
      (node (ref "JP2") (pin "4") (pinfunction "4_4") (pintype "passive"))
    )
    (net (code "97") (name "unconnected-(JP2-Pad6)") (class "Default")
      (node (ref "JP2") (pin "6") (pinfunction "6_6") (pintype "passive"))
    )
    (net (code "98") (name "unconnected-(JP2-Pad8)") (class "Default")
      (node (ref "JP2") (pin "8") (pinfunction "8_8") (pintype "passive"))
    )
    (net (code "99") (name "unconnected-(JP2-Pad10)") (class "Default")
      (node (ref "JP2") (pin "10") (pinfunction "10_10") (pintype "passive"))
    )
    (net (code "100") (name "unconnected-(JP2-Pad14)") (class "Default")
      (node (ref "JP2") (pin "14") (pinfunction "14_14") (pintype "passive"))
    )
    (net (code "101") (name "unconnected-(JP2-Pad17)") (class "Default")
      (node (ref "JP2") (pin "17") (pinfunction "17_17") (pintype "passive"))
    )
  )
)
